# analog_frontend.net
KiCad netlist of a schematic drawn in EAGLE
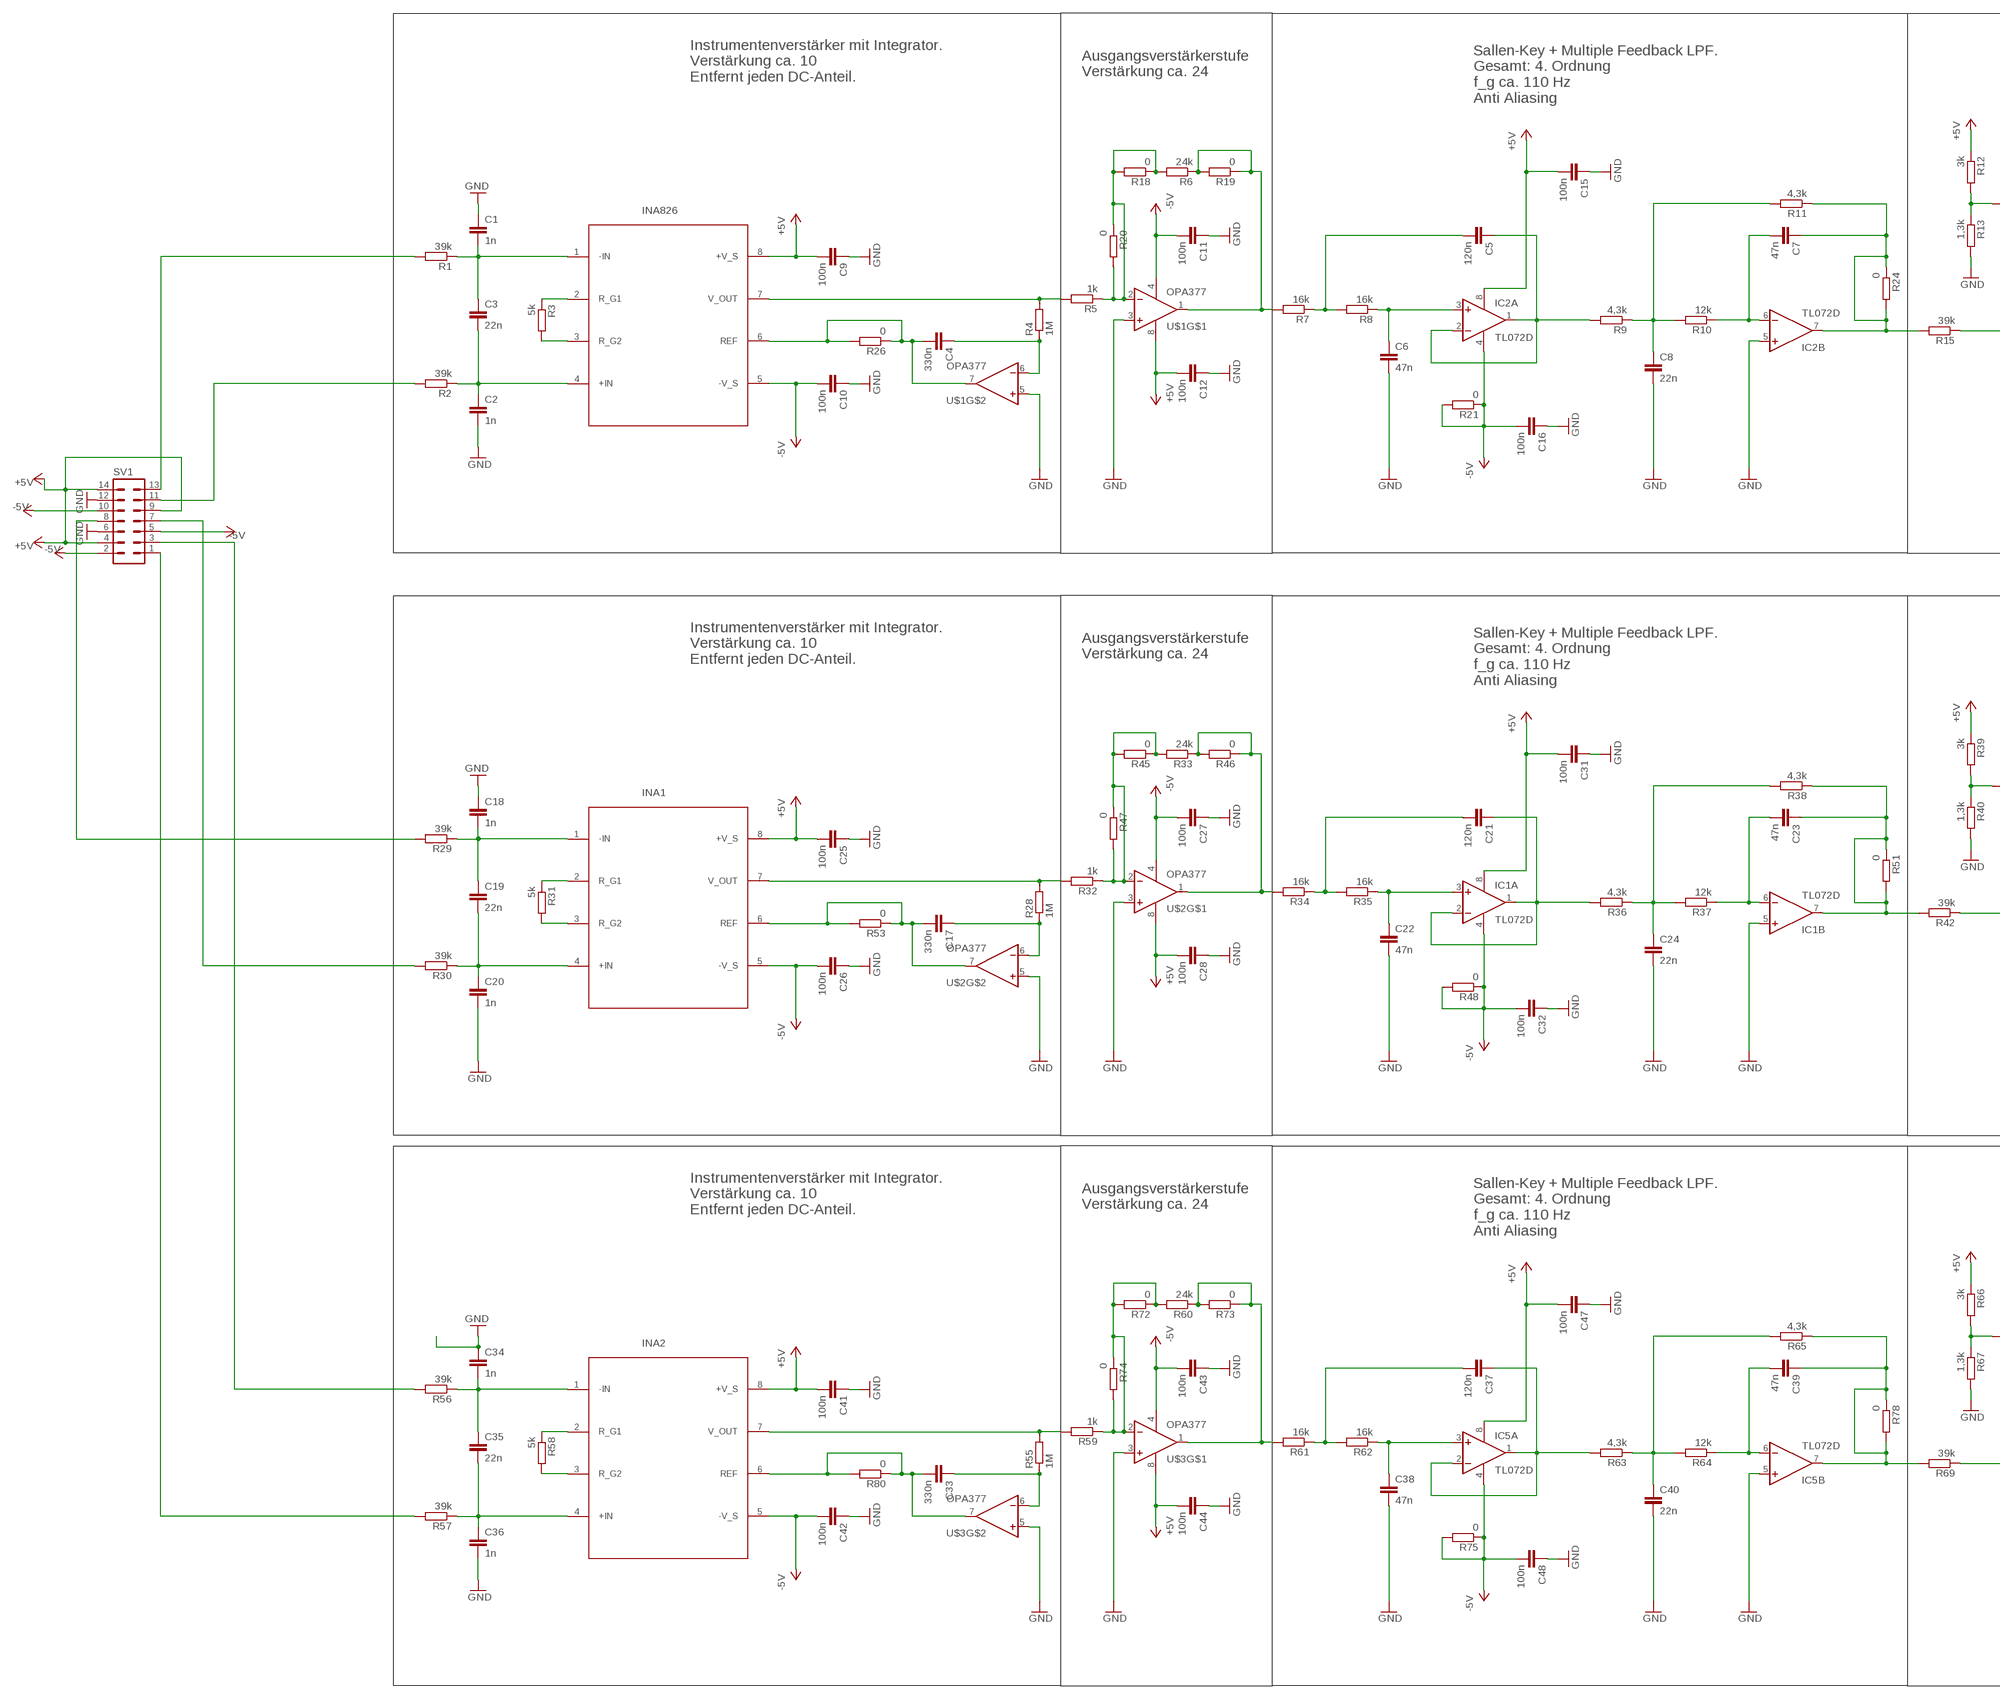
[diagram p0: schematic, sheet 1, part 1 of 2]
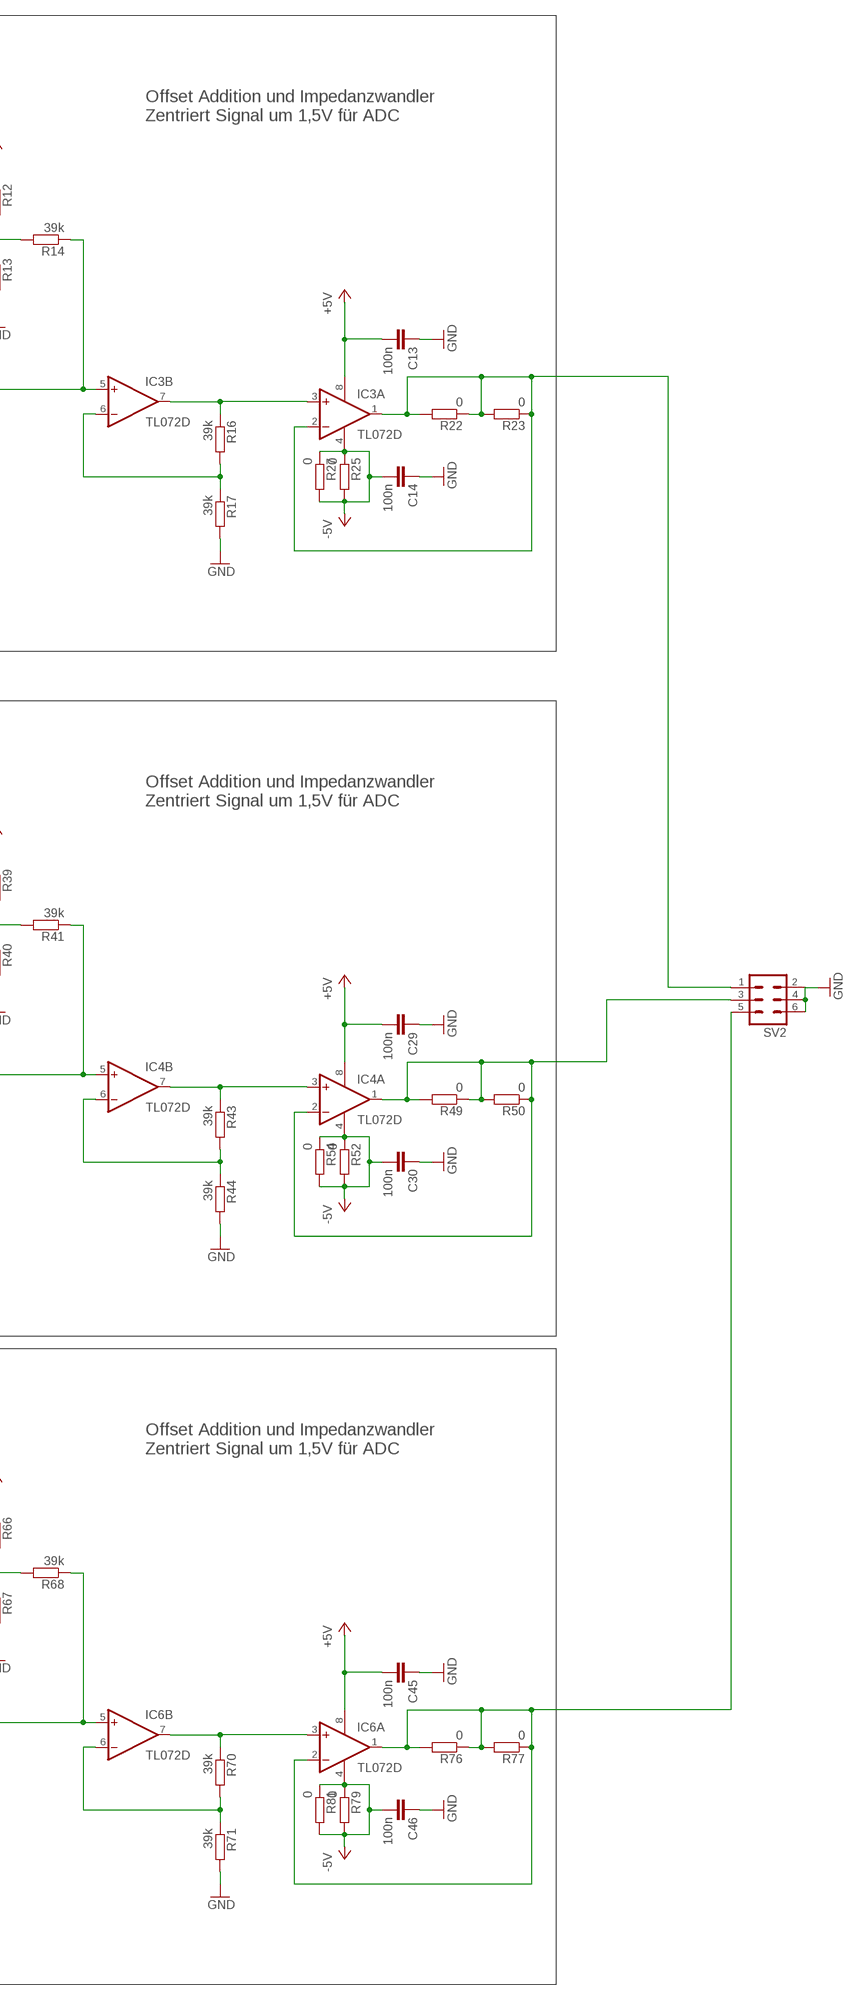
[diagram p1: schematic, sheet 1, part 2 of 2]

(export (version "E")
  (design (tool "Eeschema 10.0.6"))
  (components
    (comp (ref "C1")
      (value "1n")
      (footprint "eagle-import:C0805")
      (libsource (lib "eagle-import") (part "C-EUC0805"))
    )
    (comp (ref "C2")
      (value "1n")
      (footprint "eagle-import:C0805")
      (libsource (lib "eagle-import") (part "C-EUC0805"))
    )
    (comp (ref "C3")
      (value "22n")
      (footprint "eagle-import:C0805")
      (libsource (lib "eagle-import") (part "C-EUC0805"))
    )
    (comp (ref "C4")
      (value "330n")
      (footprint "eagle-import:C1206")
      (libsource (lib "eagle-import") (part "C-EUC1206"))
    )
    (comp (ref "C5")
      (value "120n")
      (footprint "eagle-import:C0805")
      (libsource (lib "eagle-import") (part "C-EUC0805"))
    )
    (comp (ref "C6")
      (value "47n")
      (footprint "eagle-import:C0805")
      (libsource (lib "eagle-import") (part "C-EUC0805"))
    )
    (comp (ref "C7")
      (value "47n")
      (footprint "eagle-import:C0805")
      (libsource (lib "eagle-import") (part "C-EUC0805"))
    )
    (comp (ref "C8")
      (value "22n")
      (footprint "eagle-import:C0805")
      (libsource (lib "eagle-import") (part "C-EUC0805"))
    )
    (comp (ref "C9")
      (value "100n")
      (footprint "eagle-import:C0805")
      (libsource (lib "eagle-import") (part "C-EUC0805"))
    )
    (comp (ref "C10")
      (value "100n")
      (footprint "eagle-import:C0805")
      (libsource (lib "eagle-import") (part "C-EUC0805"))
    )
    (comp (ref "C11")
      (value "100n")
      (footprint "eagle-import:C0805")
      (libsource (lib "eagle-import") (part "C-EUC0805"))
    )
    (comp (ref "C12")
      (value "100n")
      (footprint "eagle-import:C0805")
      (libsource (lib "eagle-import") (part "C-EUC0805"))
    )
    (comp (ref "C13")
      (value "100n")
      (footprint "eagle-import:C0805")
      (libsource (lib "eagle-import") (part "C-EUC0805"))
    )
    (comp (ref "C14")
      (value "100n")
      (footprint "eagle-import:C0805")
      (libsource (lib "eagle-import") (part "C-EUC0805"))
    )
    (comp (ref "C15")
      (value "100n")
      (footprint "eagle-import:C1206")
      (libsource (lib "eagle-import") (part "C-EUC1206"))
    )
    (comp (ref "C16")
      (value "100n")
      (footprint "eagle-import:C0805")
      (libsource (lib "eagle-import") (part "C-EUC0805"))
    )
    (comp (ref "C17")
      (value "330n")
      (footprint "eagle-import:C1206")
      (libsource (lib "eagle-import") (part "C-EUC1206"))
    )
    (comp (ref "C18")
      (value "1n")
      (footprint "eagle-import:C0805")
      (libsource (lib "eagle-import") (part "C-EUC0805"))
    )
    (comp (ref "C19")
      (value "22n")
      (footprint "eagle-import:C0805")
      (libsource (lib "eagle-import") (part "C-EUC0805"))
    )
    (comp (ref "C20")
      (value "1n")
      (footprint "eagle-import:C0805")
      (libsource (lib "eagle-import") (part "C-EUC0805"))
    )
    (comp (ref "C21")
      (value "120n")
      (footprint "eagle-import:C0805")
      (libsource (lib "eagle-import") (part "C-EUC0805"))
    )
    (comp (ref "C22")
      (value "47n")
      (footprint "eagle-import:C0805")
      (libsource (lib "eagle-import") (part "C-EUC0805"))
    )
    (comp (ref "C23")
      (value "47n")
      (footprint "eagle-import:C0805")
      (libsource (lib "eagle-import") (part "C-EUC0805"))
    )
    (comp (ref "C24")
      (value "22n")
      (footprint "eagle-import:C0805")
      (libsource (lib "eagle-import") (part "C-EUC0805"))
    )
    (comp (ref "C25")
      (value "100n")
      (footprint "eagle-import:C0805")
      (libsource (lib "eagle-import") (part "C-EUC0805"))
    )
    (comp (ref "C26")
      (value "100n")
      (footprint "eagle-import:C0805")
      (libsource (lib "eagle-import") (part "C-EUC0805"))
    )
    (comp (ref "C27")
      (value "100n")
      (footprint "eagle-import:C0805")
      (libsource (lib "eagle-import") (part "C-EUC0805"))
    )
    (comp (ref "C28")
      (value "100n")
      (footprint "eagle-import:C0805")
      (libsource (lib "eagle-import") (part "C-EUC0805"))
    )
    (comp (ref "C29")
      (value "100n")
      (footprint "eagle-import:C0805")
      (libsource (lib "eagle-import") (part "C-EUC0805"))
    )
    (comp (ref "C30")
      (value "100n")
      (footprint "eagle-import:C0805")
      (libsource (lib "eagle-import") (part "C-EUC0805"))
    )
    (comp (ref "C31")
      (value "100n")
      (footprint "eagle-import:C1206")
      (libsource (lib "eagle-import") (part "C-EUC1206"))
    )
    (comp (ref "C32")
      (value "100n")
      (footprint "eagle-import:C0805")
      (libsource (lib "eagle-import") (part "C-EUC0805"))
    )
    (comp (ref "C33")
      (value "330n")
      (footprint "eagle-import:C1206")
      (libsource (lib "eagle-import") (part "C-EUC1206"))
    )
    (comp (ref "C34")
      (value "1n")
      (footprint "eagle-import:C0805")
      (libsource (lib "eagle-import") (part "C-EUC0805"))
    )
    (comp (ref "C35")
      (value "22n")
      (footprint "eagle-import:C0805")
      (libsource (lib "eagle-import") (part "C-EUC0805"))
    )
    (comp (ref "C36")
      (value "1n")
      (footprint "eagle-import:C0805")
      (libsource (lib "eagle-import") (part "C-EUC0805"))
    )
    (comp (ref "C37")
      (value "120n")
      (footprint "eagle-import:C0805")
      (libsource (lib "eagle-import") (part "C-EUC0805"))
    )
    (comp (ref "C38")
      (value "47n")
      (footprint "eagle-import:C0805")
      (libsource (lib "eagle-import") (part "C-EUC0805"))
    )
    (comp (ref "C39")
      (value "47n")
      (footprint "eagle-import:C0805")
      (libsource (lib "eagle-import") (part "C-EUC0805"))
    )
    (comp (ref "C40")
      (value "22n")
      (footprint "eagle-import:C0805")
      (libsource (lib "eagle-import") (part "C-EUC0805"))
    )
    (comp (ref "C41")
      (value "100n")
      (footprint "eagle-import:C0805")
      (libsource (lib "eagle-import") (part "C-EUC0805"))
    )
    (comp (ref "C42")
      (value "100n")
      (footprint "eagle-import:C0805")
      (libsource (lib "eagle-import") (part "C-EUC0805"))
    )
    (comp (ref "C43")
      (value "100n")
      (footprint "eagle-import:C0805")
      (libsource (lib "eagle-import") (part "C-EUC0805"))
    )
    (comp (ref "C44")
      (value "100n")
      (footprint "eagle-import:C0805")
      (libsource (lib "eagle-import") (part "C-EUC0805"))
    )
    (comp (ref "C45")
      (value "100n")
      (footprint "eagle-import:C0805")
      (libsource (lib "eagle-import") (part "C-EUC0805"))
    )
    (comp (ref "C46")
      (value "100n")
      (footprint "eagle-import:C0805")
      (libsource (lib "eagle-import") (part "C-EUC0805"))
    )
    (comp (ref "C47")
      (value "100n")
      (footprint "eagle-import:C1206")
      (libsource (lib "eagle-import") (part "C-EUC1206"))
    )
    (comp (ref "C48")
      (value "100n")
      (footprint "eagle-import:C0805")
      (libsource (lib "eagle-import") (part "C-EUC0805"))
    )
    (comp (ref "IC1")
      (value "TL072D")
      (footprint "eagle-import:SO08")
      (libsource (lib "eagle-import") (part "TL072D"))
    )
    (comp (ref "IC2")
      (value "TL072D")
      (footprint "eagle-import:SO08")
      (libsource (lib "eagle-import") (part "TL072D"))
    )
    (comp (ref "IC3")
      (value "TL072D")
      (footprint "eagle-import:SO08")
      (libsource (lib "eagle-import") (part "TL072D"))
    )
    (comp (ref "IC4")
      (value "TL072D")
      (footprint "eagle-import:SO08")
      (libsource (lib "eagle-import") (part "TL072D"))
    )
    (comp (ref "IC5")
      (value "TL072D")
      (footprint "eagle-import:SO08")
      (libsource (lib "eagle-import") (part "TL072D"))
    )
    (comp (ref "IC6")
      (value "TL072D")
      (footprint "eagle-import:SO08")
      (libsource (lib "eagle-import") (part "TL072D"))
    )
    (comp (ref "INA1")
      (value "INA826")
      (footprint "eagle-import:SOIC8")
      (libsource (lib "eagle-import") (part "INA826"))
    )
    (comp (ref "INA2")
      (value "INA826")
      (footprint "eagle-import:SOIC8")
      (libsource (lib "eagle-import") (part "INA826"))
    )
    (comp (ref "INA826")
      (value "INA826")
      (footprint "eagle-import:SOIC8")
      (libsource (lib "eagle-import") (part "INA826"))
    )
    (comp (ref "R1")
      (value "39k")
      (footprint "eagle-import:R0805")
      (libsource (lib "eagle-import") (part "R-EU_R0805"))
    )
    (comp (ref "R2")
      (value "39k")
      (footprint "eagle-import:R0805")
      (libsource (lib "eagle-import") (part "R-EU_R0805"))
    )
    (comp (ref "R3")
      (value "5k")
      (footprint "eagle-import:R0805")
      (libsource (lib "eagle-import") (part "R-EU_R0805"))
    )
    (comp (ref "R4")
      (value "1M")
      (footprint "eagle-import:R1206")
      (libsource (lib "eagle-import") (part "R-EU_R1206"))
    )
    (comp (ref "R5")
      (value "1k")
      (footprint "eagle-import:R1206")
      (libsource (lib "eagle-import") (part "R-EU_R1206"))
    )
    (comp (ref "R6")
      (value "24k")
      (footprint "eagle-import:R0805")
      (libsource (lib "eagle-import") (part "R-EU_R0805"))
    )
    (comp (ref "R7")
      (value "16k")
      (footprint "eagle-import:R1206")
      (libsource (lib "eagle-import") (part "R-EU_R1206"))
    )
    (comp (ref "R8")
      (value "16k")
      (footprint "eagle-import:R0805")
      (libsource (lib "eagle-import") (part "R-EU_R0805"))
    )
    (comp (ref "R9")
      (value "4,3k")
      (footprint "eagle-import:R0805")
      (libsource (lib "eagle-import") (part "R-EU_R0805"))
    )
    (comp (ref "R10")
      (value "12k")
      (footprint "eagle-import:R0805")
      (libsource (lib "eagle-import") (part "R-EU_R0805"))
    )
    (comp (ref "R11")
      (value "4,3k")
      (footprint "eagle-import:R0805")
      (libsource (lib "eagle-import") (part "R-EU_R0805"))
    )
    (comp (ref "R12")
      (value "3k")
      (footprint "eagle-import:R0805")
      (libsource (lib "eagle-import") (part "R-EU_R0805"))
    )
    (comp (ref "R13")
      (value "1,3k")
      (footprint "eagle-import:R1206")
      (libsource (lib "eagle-import") (part "R-EU_R1206"))
    )
    (comp (ref "R14")
      (value "39k")
      (footprint "eagle-import:R0805")
      (libsource (lib "eagle-import") (part "R-EU_R0805"))
    )
    (comp (ref "R15")
      (value "39k")
      (footprint "eagle-import:R0805")
      (libsource (lib "eagle-import") (part "R-EU_R0805"))
    )
    (comp (ref "R16")
      (value "39k")
      (footprint "eagle-import:R0805")
      (libsource (lib "eagle-import") (part "R-EU_R0805"))
    )
    (comp (ref "R17")
      (value "39k")
      (footprint "eagle-import:R1206")
      (libsource (lib "eagle-import") (part "R-EU_R1206"))
    )
    (comp (ref "R18")
      (value "0")
      (footprint "eagle-import:R1206")
      (libsource (lib "eagle-import") (part "R-EU_R1206"))
    )
    (comp (ref "R19")
      (value "0")
      (footprint "eagle-import:R1206")
      (libsource (lib "eagle-import") (part "R-EU_R1206"))
    )
    (comp (ref "R20")
      (value "0")
      (footprint "eagle-import:R1206")
      (libsource (lib "eagle-import") (part "R-EU_R1206"))
    )
    (comp (ref "R21")
      (value "0")
      (footprint "eagle-import:R1206")
      (libsource (lib "eagle-import") (part "R-EU_R1206"))
    )
    (comp (ref "R22")
      (value "0")
      (footprint "eagle-import:R1206")
      (libsource (lib "eagle-import") (part "R-EU_R1206"))
    )
    (comp (ref "R23")
      (value "0")
      (footprint "eagle-import:R1206")
      (libsource (lib "eagle-import") (part "R-EU_R1206"))
    )
    (comp (ref "R24")
      (value "0")
      (footprint "eagle-import:R1206")
      (libsource (lib "eagle-import") (part "R-EU_R1206"))
    )
    (comp (ref "R25")
      (value "0")
      (footprint "eagle-import:R1206")
      (libsource (lib "eagle-import") (part "R-EU_R1206"))
    )
    (comp (ref "R26")
      (value "0")
      (footprint "eagle-import:R1206")
      (libsource (lib "eagle-import") (part "R-EU_R1206"))
    )
    (comp (ref "R27")
      (value "0")
      (footprint "eagle-import:R1206")
      (libsource (lib "eagle-import") (part "R-EU_R1206"))
    )
    (comp (ref "R28")
      (value "1M")
      (footprint "eagle-import:R1206")
      (libsource (lib "eagle-import") (part "R-EU_R1206"))
    )
    (comp (ref "R29")
      (value "39k")
      (footprint "eagle-import:R0805")
      (libsource (lib "eagle-import") (part "R-EU_R0805"))
    )
    (comp (ref "R30")
      (value "39k")
      (footprint "eagle-import:R0805")
      (libsource (lib "eagle-import") (part "R-EU_R0805"))
    )
    (comp (ref "R31")
      (value "5k")
      (footprint "eagle-import:R0805")
      (libsource (lib "eagle-import") (part "R-EU_R0805"))
    )
    (comp (ref "R32")
      (value "1k")
      (footprint "eagle-import:R1206")
      (libsource (lib "eagle-import") (part "R-EU_R1206"))
    )
    (comp (ref "R33")
      (value "24k")
      (footprint "eagle-import:R0805")
      (libsource (lib "eagle-import") (part "R-EU_R0805"))
    )
    (comp (ref "R34")
      (value "16k")
      (footprint "eagle-import:R1206")
      (libsource (lib "eagle-import") (part "R-EU_R1206"))
    )
    (comp (ref "R35")
      (value "16k")
      (footprint "eagle-import:R0805")
      (libsource (lib "eagle-import") (part "R-EU_R0805"))
    )
    (comp (ref "R36")
      (value "4,3k")
      (footprint "eagle-import:R0805")
      (libsource (lib "eagle-import") (part "R-EU_R0805"))
    )
    (comp (ref "R37")
      (value "12k")
      (footprint "eagle-import:R0805")
      (libsource (lib "eagle-import") (part "R-EU_R0805"))
    )
    (comp (ref "R38")
      (value "4,3k")
      (footprint "eagle-import:R0805")
      (libsource (lib "eagle-import") (part "R-EU_R0805"))
    )
    (comp (ref "R39")
      (value "3k")
      (footprint "eagle-import:R0805")
      (libsource (lib "eagle-import") (part "R-EU_R0805"))
    )
    (comp (ref "R40")
      (value "1,3k")
      (footprint "eagle-import:R1206")
      (libsource (lib "eagle-import") (part "R-EU_R1206"))
    )
    (comp (ref "R41")
      (value "39k")
      (footprint "eagle-import:R0805")
      (libsource (lib "eagle-import") (part "R-EU_R0805"))
    )
    (comp (ref "R42")
      (value "39k")
      (footprint "eagle-import:R0805")
      (libsource (lib "eagle-import") (part "R-EU_R0805"))
    )
    (comp (ref "R43")
      (value "39k")
      (footprint "eagle-import:R0805")
      (libsource (lib "eagle-import") (part "R-EU_R0805"))
    )
    (comp (ref "R44")
      (value "39k")
      (footprint "eagle-import:R1206")
      (libsource (lib "eagle-import") (part "R-EU_R1206"))
    )
    (comp (ref "R45")
      (value "0")
      (footprint "eagle-import:R1206")
      (libsource (lib "eagle-import") (part "R-EU_R1206"))
    )
    (comp (ref "R46")
      (value "0")
      (footprint "eagle-import:R1206")
      (libsource (lib "eagle-import") (part "R-EU_R1206"))
    )
    (comp (ref "R47")
      (value "0")
      (footprint "eagle-import:R1206")
      (libsource (lib "eagle-import") (part "R-EU_R1206"))
    )
    (comp (ref "R48")
      (value "0")
      (footprint "eagle-import:R1206")
      (libsource (lib "eagle-import") (part "R-EU_R1206"))
    )
    (comp (ref "R49")
      (value "0")
      (footprint "eagle-import:R1206")
      (libsource (lib "eagle-import") (part "R-EU_R1206"))
    )
    (comp (ref "R50")
      (value "0")
      (footprint "eagle-import:R1206")
      (libsource (lib "eagle-import") (part "R-EU_R1206"))
    )
    (comp (ref "R51")
      (value "0")
      (footprint "eagle-import:R1206")
      (libsource (lib "eagle-import") (part "R-EU_R1206"))
    )
    (comp (ref "R52")
      (value "0")
      (footprint "eagle-import:R1206")
      (libsource (lib "eagle-import") (part "R-EU_R1206"))
    )
    (comp (ref "R53")
      (value "0")
      (footprint "eagle-import:R1206")
      (libsource (lib "eagle-import") (part "R-EU_R1206"))
    )
    (comp (ref "R54")
      (value "0")
      (footprint "eagle-import:R1206")
      (libsource (lib "eagle-import") (part "R-EU_R1206"))
    )
    (comp (ref "R55")
      (value "1M")
      (footprint "eagle-import:R1206")
      (libsource (lib "eagle-import") (part "R-EU_R1206"))
    )
    (comp (ref "R56")
      (value "39k")
      (footprint "eagle-import:R0805")
      (libsource (lib "eagle-import") (part "R-EU_R0805"))
    )
    (comp (ref "R57")
      (value "39k")
      (footprint "eagle-import:R0805")
      (libsource (lib "eagle-import") (part "R-EU_R0805"))
    )
    (comp (ref "R58")
      (value "5k")
      (footprint "eagle-import:R0805")
      (libsource (lib "eagle-import") (part "R-EU_R0805"))
    )
    (comp (ref "R59")
      (value "1k")
      (footprint "eagle-import:R1206")
      (libsource (lib "eagle-import") (part "R-EU_R1206"))
    )
    (comp (ref "R60")
      (value "24k")
      (footprint "eagle-import:R0805")
      (libsource (lib "eagle-import") (part "R-EU_R0805"))
    )
    (comp (ref "R61")
      (value "16k")
      (footprint "eagle-import:R1206")
      (libsource (lib "eagle-import") (part "R-EU_R1206"))
    )
    (comp (ref "R62")
      (value "16k")
      (footprint "eagle-import:R0805")
      (libsource (lib "eagle-import") (part "R-EU_R0805"))
    )
    (comp (ref "R63")
      (value "4,3k")
      (footprint "eagle-import:R0805")
      (libsource (lib "eagle-import") (part "R-EU_R0805"))
    )
    (comp (ref "R64")
      (value "12k")
      (footprint "eagle-import:R0805")
      (libsource (lib "eagle-import") (part "R-EU_R0805"))
    )
    (comp (ref "R65")
      (value "4,3k")
      (footprint "eagle-import:R0805")
      (libsource (lib "eagle-import") (part "R-EU_R0805"))
    )
    (comp (ref "R66")
      (value "3k")
      (footprint "eagle-import:R0805")
      (libsource (lib "eagle-import") (part "R-EU_R0805"))
    )
    (comp (ref "R67")
      (value "1,3k")
      (footprint "eagle-import:R1206")
      (libsource (lib "eagle-import") (part "R-EU_R1206"))
    )
    (comp (ref "R68")
      (value "39k")
      (footprint "eagle-import:R0805")
      (libsource (lib "eagle-import") (part "R-EU_R0805"))
    )
    (comp (ref "R69")
      (value "39k")
      (footprint "eagle-import:R0805")
      (libsource (lib "eagle-import") (part "R-EU_R0805"))
    )
    (comp (ref "R70")
      (value "39k")
      (footprint "eagle-import:R0805")
      (libsource (lib "eagle-import") (part "R-EU_R0805"))
    )
    (comp (ref "R71")
      (value "39k")
      (footprint "eagle-import:R1206")
      (libsource (lib "eagle-import") (part "R-EU_R1206"))
    )
    (comp (ref "R72")
      (value "0")
      (footprint "eagle-import:R1206")
      (libsource (lib "eagle-import") (part "R-EU_R1206"))
    )
    (comp (ref "R73")
      (value "0")
      (footprint "eagle-import:R1206")
      (libsource (lib "eagle-import") (part "R-EU_R1206"))
    )
    (comp (ref "R74")
      (value "0")
      (footprint "eagle-import:R1206")
      (libsource (lib "eagle-import") (part "R-EU_R1206"))
    )
    (comp (ref "R75")
      (value "0")
      (footprint "eagle-import:R1206")
      (libsource (lib "eagle-import") (part "R-EU_R1206"))
    )
    (comp (ref "R76")
      (value "0")
      (footprint "eagle-import:R1206")
      (libsource (lib "eagle-import") (part "R-EU_R1206"))
    )
    (comp (ref "R77")
      (value "0")
      (footprint "eagle-import:R1206")
      (libsource (lib "eagle-import") (part "R-EU_R1206"))
    )
    (comp (ref "R78")
      (value "0")
      (footprint "eagle-import:R1206")
      (libsource (lib "eagle-import") (part "R-EU_R1206"))
    )
    (comp (ref "R79")
      (value "0")
      (footprint "eagle-import:R1206")
      (libsource (lib "eagle-import") (part "R-EU_R1206"))
    )
    (comp (ref "R80")
      (value "0")
      (footprint "eagle-import:R1206")
      (libsource (lib "eagle-import") (part "R-EU_R1206"))
    )
    (comp (ref "R81")
      (value "0")
      (footprint "eagle-import:R1206")
      (libsource (lib "eagle-import") (part "R-EU_R1206"))
    )
    (comp (ref "SV1")
      (value "ML14L")
      (footprint "eagle-import:ML14L")
      (libsource (lib "eagle-import") (part "ML14L"))
    )
    (comp (ref "SV2")
      (value "ML6L")
      (footprint "eagle-import:ML6L")
      (libsource (lib "eagle-import") (part "ML6L"))
    )
    (comp (ref "U$1")
      (value "OPA377")
      (footprint "eagle-import:SOIC8")
      (libsource (lib "eagle-import") (part "OPA377"))
    )
    (comp (ref "U$2")
      (value "OPA377")
      (footprint "eagle-import:SOIC8")
      (libsource (lib "eagle-import") (part "OPA377"))
    )
    (comp (ref "U$3")
      (value "OPA377")
      (footprint "eagle-import:SOIC8")
      (libsource (lib "eagle-import") (part "OPA377"))
    )
  )
  (nets
    (net (code "1") (name "+5V") (class "Default")
      (node (ref "C12") (pin "2") (pinfunction "2_2") (pintype "passive"))
      (node (ref "C13") (pin "2") (pinfunction "2_2") (pintype "passive"))
      (node (ref "C15") (pin "2") (pinfunction "2_2") (pintype "passive"))
      (node (ref "C25") (pin "2") (pinfunction "2_2") (pintype "passive"))
      (node (ref "C28") (pin "2") (pinfunction "2_2") (pintype "passive"))
      (node (ref "C29") (pin "2") (pinfunction "2_2") (pintype "passive"))
      (node (ref "C31") (pin "2") (pinfunction "2_2") (pintype "passive"))
      (node (ref "C41") (pin "2") (pinfunction "2_2") (pintype "passive"))
      (node (ref "C44") (pin "2") (pinfunction "2_2") (pintype "passive"))
      (node (ref "C45") (pin "2") (pinfunction "2_2") (pintype "passive"))
      (node (ref "C47") (pin "2") (pinfunction "2_2") (pintype "passive"))
      (node (ref "C9") (pin "2") (pinfunction "2_2") (pintype "passive"))
      (node (ref "IC1") (pin "8") (pinfunction "V+_8") (pintype "power_in"))
      (node (ref "IC2") (pin "8") (pinfunction "V+_8") (pintype "power_in"))
      (node (ref "IC3") (pin "8") (pinfunction "V+_8") (pintype "power_in"))
      (node (ref "IC4") (pin "8") (pinfunction "V+_8") (pintype "power_in"))
      (node (ref "IC5") (pin "8") (pinfunction "V+_8") (pintype "power_in"))
      (node (ref "IC6") (pin "8") (pinfunction "V+_8") (pintype "power_in"))
      (node (ref "INA1") (pin "8") (pinfunction "+V_S_8") (pintype "power_in"))
      (node (ref "INA2") (pin "8") (pinfunction "+V_S_8") (pintype "power_in"))
      (node (ref "INA826") (pin "8") (pinfunction "+V_S_8") (pintype "power_in"))
      (node (ref "R12") (pin "1") (pinfunction "1_1") (pintype "passive"))
      (node (ref "R39") (pin "1") (pinfunction "1_1") (pintype "passive"))
      (node (ref "R66") (pin "1") (pinfunction "1_1") (pintype "passive"))
      (node (ref "SV1") (pin "14") (pinfunction "14_14") (pintype "passive"))
      (node (ref "SV1") (pin "4") (pinfunction "4_4") (pintype "passive"))
      (node (ref "SV1") (pin "9") (pinfunction "9_9") (pintype "passive"))
      (node (ref "U$1") (pin "8") (pinfunction "V+_8") (pintype "power_in"))
      (node (ref "U$2") (pin "8") (pinfunction "V+_8") (pintype "power_in"))
      (node (ref "U$3") (pin "8") (pinfunction "V+_8") (pintype "power_in"))
    )
    (net (code "2") (name "-5V") (class "Default")
      (node (ref "C10") (pin "2") (pinfunction "2_2") (pintype "passive"))
      (node (ref "C11") (pin "2") (pinfunction "2_2") (pintype "passive"))
      (node (ref "C14") (pin "2") (pinfunction "2_2") (pintype "passive"))
      (node (ref "C16") (pin "2") (pinfunction "2_2") (pintype "passive"))
      (node (ref "C26") (pin "2") (pinfunction "2_2") (pintype "passive"))
      (node (ref "C27") (pin "2") (pinfunction "2_2") (pintype "passive"))
      (node (ref "C30") (pin "2") (pinfunction "2_2") (pintype "passive"))
      (node (ref "C32") (pin "2") (pinfunction "2_2") (pintype "passive"))
      (node (ref "C42") (pin "2") (pinfunction "2_2") (pintype "passive"))
      (node (ref "C43") (pin "2") (pinfunction "2_2") (pintype "passive"))
      (node (ref "C46") (pin "2") (pinfunction "2_2") (pintype "passive"))
      (node (ref "C48") (pin "2") (pinfunction "2_2") (pintype "passive"))
      (node (ref "IC1") (pin "4") (pinfunction "V-_4") (pintype "power_in"))
      (node (ref "IC2") (pin "4") (pinfunction "V-_4") (pintype "power_in"))
      (node (ref "IC3") (pin "4") (pinfunction "V-_4") (pintype "power_in"))
      (node (ref "IC4") (pin "4") (pinfunction "V-_4") (pintype "power_in"))
      (node (ref "IC5") (pin "4") (pinfunction "V-_4") (pintype "power_in"))
      (node (ref "IC6") (pin "4") (pinfunction "V-_4") (pintype "power_in"))
      (node (ref "INA1") (pin "5") (pinfunction "-V_S_5") (pintype "power_in"))
      (node (ref "INA2") (pin "5") (pinfunction "-V_S_5") (pintype "power_in"))
      (node (ref "INA826") (pin "5") (pinfunction "-V_S_5") (pintype "power_in"))
      (node (ref "R21") (pin "1") (pinfunction "1_1") (pintype "passive"))
      (node (ref "R21") (pin "2") (pinfunction "2_2") (pintype "passive"))
      (node (ref "R25") (pin "1") (pinfunction "1_1") (pintype "passive"))
      (node (ref "R25") (pin "2") (pinfunction "2_2") (pintype "passive"))
      (node (ref "R27") (pin "1") (pinfunction "1_1") (pintype "passive"))
      (node (ref "R27") (pin "2") (pinfunction "2_2") (pintype "passive"))
      (node (ref "R48") (pin "1") (pinfunction "1_1") (pintype "passive"))
      (node (ref "R48") (pin "2") (pinfunction "2_2") (pintype "passive"))
      (node (ref "R52") (pin "1") (pinfunction "1_1") (pintype "passive"))
      (node (ref "R52") (pin "2") (pinfunction "2_2") (pintype "passive"))
      (node (ref "R54") (pin "1") (pinfunction "1_1") (pintype "passive"))
      (node (ref "R54") (pin "2") (pinfunction "2_2") (pintype "passive"))
      (node (ref "R75") (pin "1") (pinfunction "1_1") (pintype "passive"))
      (node (ref "R75") (pin "2") (pinfunction "2_2") (pintype "passive"))
      (node (ref "R79") (pin "1") (pinfunction "1_1") (pintype "passive"))
      (node (ref "R79") (pin "2") (pinfunction "2_2") (pintype "passive"))
      (node (ref "R81") (pin "1") (pinfunction "1_1") (pintype "passive"))
      (node (ref "R81") (pin "2") (pinfunction "2_2") (pintype "passive"))
      (node (ref "SV1") (pin "10") (pinfunction "10_10") (pintype "passive"))
      (node (ref "SV1") (pin "2") (pinfunction "2_2") (pintype "passive"))
      (node (ref "SV1") (pin "5") (pinfunction "5_5") (pintype "passive"))
      (node (ref "U$1") (pin "4") (pinfunction "V-_4") (pintype "power_in"))
      (node (ref "U$2") (pin "4") (pinfunction "V-_4") (pintype "power_in"))
      (node (ref "U$3") (pin "4") (pinfunction "V-_4") (pintype "power_in"))
    )
    (net (code "3") (name "GND") (class "Default")
      (node (ref "C1") (pin "1") (pinfunction "1_1") (pintype "passive"))
      (node (ref "C10") (pin "1") (pinfunction "1_1") (pintype "passive"))
      (node (ref "C11") (pin "1") (pinfunction "1_1") (pintype "passive"))
      (node (ref "C12") (pin "1") (pinfunction "1_1") (pintype "passive"))
      (node (ref "C13") (pin "1") (pinfunction "1_1") (pintype "passive"))
      (node (ref "C14") (pin "1") (pinfunction "1_1") (pintype "passive"))
      (node (ref "C15") (pin "1") (pinfunction "1_1") (pintype "passive"))
      (node (ref "C16") (pin "1") (pinfunction "1_1") (pintype "passive"))
      (node (ref "C18") (pin "1") (pinfunction "1_1") (pintype "passive"))
      (node (ref "C2") (pin "2") (pinfunction "2_2") (pintype "passive"))
      (node (ref "C20") (pin "2") (pinfunction "2_2") (pintype "passive"))
      (node (ref "C22") (pin "2") (pinfunction "2_2") (pintype "passive"))
      (node (ref "C24") (pin "2") (pinfunction "2_2") (pintype "passive"))
      (node (ref "C25") (pin "1") (pinfunction "1_1") (pintype "passive"))
      (node (ref "C26") (pin "1") (pinfunction "1_1") (pintype "passive"))
      (node (ref "C27") (pin "1") (pinfunction "1_1") (pintype "passive"))
      (node (ref "C28") (pin "1") (pinfunction "1_1") (pintype "passive"))
      (node (ref "C29") (pin "1") (pinfunction "1_1") (pintype "passive"))
      (node (ref "C30") (pin "1") (pinfunction "1_1") (pintype "passive"))
      (node (ref "C31") (pin "1") (pinfunction "1_1") (pintype "passive"))
      (node (ref "C32") (pin "1") (pinfunction "1_1") (pintype "passive"))
      (node (ref "C34") (pin "1") (pinfunction "1_1") (pintype "passive"))
      (node (ref "C36") (pin "2") (pinfunction "2_2") (pintype "passive"))
      (node (ref "C38") (pin "2") (pinfunction "2_2") (pintype "passive"))
      (node (ref "C40") (pin "2") (pinfunction "2_2") (pintype "passive"))
      (node (ref "C41") (pin "1") (pinfunction "1_1") (pintype "passive"))
      (node (ref "C42") (pin "1") (pinfunction "1_1") (pintype "passive"))
      (node (ref "C43") (pin "1") (pinfunction "1_1") (pintype "passive"))
      (node (ref "C44") (pin "1") (pinfunction "1_1") (pintype "passive"))
      (node (ref "C45") (pin "1") (pinfunction "1_1") (pintype "passive"))
      (node (ref "C46") (pin "1") (pinfunction "1_1") (pintype "passive"))
      (node (ref "C47") (pin "1") (pinfunction "1_1") (pintype "passive"))
      (node (ref "C48") (pin "1") (pinfunction "1_1") (pintype "passive"))
      (node (ref "C6") (pin "2") (pinfunction "2_2") (pintype "passive"))
      (node (ref "C8") (pin "2") (pinfunction "2_2") (pintype "passive"))
      (node (ref "C9") (pin "1") (pinfunction "1_1") (pintype "passive"))
      (node (ref "IC1") (pin "5") (pinfunction "+IN_5") (pintype "input"))
      (node (ref "IC2") (pin "5") (pinfunction "+IN_5") (pintype "input"))
      (node (ref "IC5") (pin "5") (pinfunction "+IN_5") (pintype "input"))
      (node (ref "R13") (pin "2") (pinfunction "2_2") (pintype "passive"))
      (node (ref "R17") (pin "2") (pinfunction "2_2") (pintype "passive"))
      (node (ref "R40") (pin "2") (pinfunction "2_2") (pintype "passive"))
      (node (ref "R44") (pin "2") (pinfunction "2_2") (pintype "passive"))
      (node (ref "R67") (pin "2") (pinfunction "2_2") (pintype "passive"))
      (node (ref "R71") (pin "2") (pinfunction "2_2") (pintype "passive"))
      (node (ref "SV1") (pin "12") (pinfunction "12_12") (pintype "passive"))
      (node (ref "SV1") (pin "6") (pinfunction "6_6") (pintype "passive"))
      (node (ref "SV2") (pin "2") (pinfunction "2_2") (pintype "passive"))
      (node (ref "SV2") (pin "4") (pinfunction "4_4") (pintype "passive"))
      (node (ref "SV2") (pin "6") (pinfunction "6_6") (pintype "passive"))
      (node (ref "U$1") (pin "3") (pinfunction "+IN_3") (pintype "input"))
      (node (ref "U$1") (pin "5") (pinfunction "+IN_5") (pintype "input"))
      (node (ref "U$2") (pin "3") (pinfunction "+IN_3") (pintype "input"))
      (node (ref "U$2") (pin "5") (pinfunction "+IN_5") (pintype "input"))
      (node (ref "U$3") (pin "3") (pinfunction "+IN_3") (pintype "input"))
      (node (ref "U$3") (pin "5") (pinfunction "+IN_5") (pintype "input"))
    )
    (net (code "4") (name "Net-(C5-Pad2)") (class "Default")
      (node (ref "C5") (pin "2") (pinfunction "2_2") (pintype "passive"))
      (node (ref "R7") (pin "1") (pinfunction "1_1") (pintype "passive"))
      (node (ref "R8") (pin "2") (pinfunction "2_2") (pintype "passive"))
    )
    (net (code "5") (name "Net-(C8-Pad1)") (class "Default")
      (node (ref "C8") (pin "1") (pinfunction "1_1") (pintype "passive"))
      (node (ref "R10") (pin "2") (pinfunction "2_2") (pintype "passive"))
      (node (ref "R11") (pin "2") (pinfunction "2_2") (pintype "passive"))
      (node (ref "R9") (pin "1") (pinfunction "1_1") (pintype "passive"))
    )
    (net (code "6") (name "Net-(C21-Pad2)") (class "Default")
      (node (ref "C21") (pin "2") (pinfunction "2_2") (pintype "passive"))
      (node (ref "R34") (pin "1") (pinfunction "1_1") (pintype "passive"))
      (node (ref "R35") (pin "2") (pinfunction "2_2") (pintype "passive"))
    )
    (net (code "7") (name "Net-(C24-Pad1)") (class "Default")
      (node (ref "C24") (pin "1") (pinfunction "1_1") (pintype "passive"))
      (node (ref "R36") (pin "1") (pinfunction "1_1") (pintype "passive"))
      (node (ref "R37") (pin "2") (pinfunction "2_2") (pintype "passive"))
      (node (ref "R38") (pin "2") (pinfunction "2_2") (pintype "passive"))
    )
    (net (code "8") (name "Net-(C37-Pad2)") (class "Default")
      (node (ref "C37") (pin "2") (pinfunction "2_2") (pintype "passive"))
      (node (ref "R61") (pin "1") (pinfunction "1_1") (pintype "passive"))
      (node (ref "R62") (pin "2") (pinfunction "2_2") (pintype "passive"))
    )
    (net (code "9") (name "Net-(C40-Pad1)") (class "Default")
      (node (ref "C40") (pin "1") (pinfunction "1_1") (pintype "passive"))
      (node (ref "R63") (pin "1") (pinfunction "1_1") (pintype "passive"))
      (node (ref "R64") (pin "2") (pinfunction "2_2") (pintype "passive"))
      (node (ref "R65") (pin "2") (pinfunction "2_2") (pintype "passive"))
    )
    (net (code "10") (name "Net-(IC1A-+IN)") (class "Default")
      (node (ref "C22") (pin "1") (pinfunction "1_1") (pintype "passive"))
      (node (ref "IC1") (pin "3") (pinfunction "+IN_3") (pintype "input"))
      (node (ref "R35") (pin "1") (pinfunction "1_1") (pintype "passive"))
    )
    (net (code "11") (name "Net-(IC1A--IN)") (class "Default")
      (node (ref "C21") (pin "1") (pinfunction "1_1") (pintype "passive"))
      (node (ref "IC1") (pin "1") (pinfunction "OUT_1") (pintype "output"))
      (node (ref "IC1") (pin "2") (pinfunction "-IN_2") (pintype "input"))
      (node (ref "R36") (pin "2") (pinfunction "2_2") (pintype "passive"))
    )
    (net (code "12") (name "Net-(IC1B--IN)") (class "Default")
      (node (ref "C23") (pin "2") (pinfunction "2_2") (pintype "passive"))
      (node (ref "IC1") (pin "6") (pinfunction "-IN_6") (pintype "input"))
      (node (ref "R37") (pin "1") (pinfunction "1_1") (pintype "passive"))
    )
    (net (code "13") (name "Net-(IC1B-OUT)") (class "Default")
      (node (ref "C23") (pin "1") (pinfunction "1_1") (pintype "passive"))
      (node (ref "IC1") (pin "7") (pinfunction "OUT_7") (pintype "output"))
      (node (ref "R38") (pin "1") (pinfunction "1_1") (pintype "passive"))
      (node (ref "R42") (pin "2") (pinfunction "2_2") (pintype "passive"))
      (node (ref "R51") (pin "1") (pinfunction "1_1") (pintype "passive"))
      (node (ref "R51") (pin "2") (pinfunction "2_2") (pintype "passive"))
    )
    (net (code "14") (name "Net-(IC2A-+IN)") (class "Default")
      (node (ref "C6") (pin "1") (pinfunction "1_1") (pintype "passive"))
      (node (ref "IC2") (pin "3") (pinfunction "+IN_3") (pintype "input"))
      (node (ref "R8") (pin "1") (pinfunction "1_1") (pintype "passive"))
    )
    (net (code "15") (name "Net-(IC2A--IN)") (class "Default")
      (node (ref "C5") (pin "1") (pinfunction "1_1") (pintype "passive"))
      (node (ref "IC2") (pin "1") (pinfunction "OUT_1") (pintype "output"))
      (node (ref "IC2") (pin "2") (pinfunction "-IN_2") (pintype "input"))
      (node (ref "R9") (pin "2") (pinfunction "2_2") (pintype "passive"))
    )
    (net (code "16") (name "Net-(IC2B--IN)") (class "Default")
      (node (ref "C7") (pin "2") (pinfunction "2_2") (pintype "passive"))
      (node (ref "IC2") (pin "6") (pinfunction "-IN_6") (pintype "input"))
      (node (ref "R10") (pin "1") (pinfunction "1_1") (pintype "passive"))
    )
    (net (code "17") (name "Net-(IC2B-OUT)") (class "Default")
      (node (ref "C7") (pin "1") (pinfunction "1_1") (pintype "passive"))
      (node (ref "IC2") (pin "7") (pinfunction "OUT_7") (pintype "output"))
      (node (ref "R11") (pin "1") (pinfunction "1_1") (pintype "passive"))
      (node (ref "R15") (pin "2") (pinfunction "2_2") (pintype "passive"))
      (node (ref "R24") (pin "1") (pinfunction "1_1") (pintype "passive"))
      (node (ref "R24") (pin "2") (pinfunction "2_2") (pintype "passive"))
    )
    (net (code "18") (name "Net-(IC3A-+IN)") (class "Default")
      (node (ref "IC3") (pin "3") (pinfunction "+IN_3") (pintype "input"))
      (node (ref "IC3") (pin "7") (pinfunction "OUT_7") (pintype "output"))
      (node (ref "R16") (pin "1") (pinfunction "1_1") (pintype "passive"))
    )
    (net (code "19") (name "Net-(IC3A--IN)") (class "Default")
      (node (ref "IC3") (pin "1") (pinfunction "OUT_1") (pintype "output"))
      (node (ref "IC3") (pin "2") (pinfunction "-IN_2") (pintype "input"))
      (node (ref "R22") (pin "1") (pinfunction "1_1") (pintype "passive"))
      (node (ref "R22") (pin "2") (pinfunction "2_2") (pintype "passive"))
      (node (ref "R23") (pin "1") (pinfunction "1_1") (pintype "passive"))
      (node (ref "R23") (pin "2") (pinfunction "2_2") (pintype "passive"))
      (node (ref "SV2") (pin "1") (pinfunction "1_1") (pintype "passive"))
    )
    (net (code "20") (name "Net-(IC3B-+IN)") (class "Default")
      (node (ref "IC3") (pin "5") (pinfunction "+IN_5") (pintype "input"))
      (node (ref "R14") (pin "1") (pinfunction "1_1") (pintype "passive"))
      (node (ref "R15") (pin "1") (pinfunction "1_1") (pintype "passive"))
    )
    (net (code "21") (name "Net-(IC3B--IN)") (class "Default")
      (node (ref "IC3") (pin "6") (pinfunction "-IN_6") (pintype "input"))
      (node (ref "R16") (pin "2") (pinfunction "2_2") (pintype "passive"))
      (node (ref "R17") (pin "1") (pinfunction "1_1") (pintype "passive"))
    )
    (net (code "22") (name "Net-(IC4A-+IN)") (class "Default")
      (node (ref "IC4") (pin "3") (pinfunction "+IN_3") (pintype "input"))
      (node (ref "IC4") (pin "7") (pinfunction "OUT_7") (pintype "output"))
      (node (ref "R43") (pin "1") (pinfunction "1_1") (pintype "passive"))
    )
    (net (code "23") (name "Net-(IC4A--IN)") (class "Default")
      (node (ref "IC4") (pin "1") (pinfunction "OUT_1") (pintype "output"))
      (node (ref "IC4") (pin "2") (pinfunction "-IN_2") (pintype "input"))
      (node (ref "R49") (pin "1") (pinfunction "1_1") (pintype "passive"))
      (node (ref "R49") (pin "2") (pinfunction "2_2") (pintype "passive"))
      (node (ref "R50") (pin "1") (pinfunction "1_1") (pintype "passive"))
      (node (ref "R50") (pin "2") (pinfunction "2_2") (pintype "passive"))
      (node (ref "SV2") (pin "3") (pinfunction "3_3") (pintype "passive"))
    )
    (net (code "24") (name "Net-(IC4B-+IN)") (class "Default")
      (node (ref "IC4") (pin "5") (pinfunction "+IN_5") (pintype "input"))
      (node (ref "R41") (pin "1") (pinfunction "1_1") (pintype "passive"))
      (node (ref "R42") (pin "1") (pinfunction "1_1") (pintype "passive"))
    )
    (net (code "25") (name "Net-(IC4B--IN)") (class "Default")
      (node (ref "IC4") (pin "6") (pinfunction "-IN_6") (pintype "input"))
      (node (ref "R43") (pin "2") (pinfunction "2_2") (pintype "passive"))
      (node (ref "R44") (pin "1") (pinfunction "1_1") (pintype "passive"))
    )
    (net (code "26") (name "Net-(IC5A-+IN)") (class "Default")
      (node (ref "C38") (pin "1") (pinfunction "1_1") (pintype "passive"))
      (node (ref "IC5") (pin "3") (pinfunction "+IN_3") (pintype "input"))
      (node (ref "R62") (pin "1") (pinfunction "1_1") (pintype "passive"))
    )
    (net (code "27") (name "Net-(IC5A--IN)") (class "Default")
      (node (ref "C37") (pin "1") (pinfunction "1_1") (pintype "passive"))
      (node (ref "IC5") (pin "1") (pinfunction "OUT_1") (pintype "output"))
      (node (ref "IC5") (pin "2") (pinfunction "-IN_2") (pintype "input"))
      (node (ref "R63") (pin "2") (pinfunction "2_2") (pintype "passive"))
    )
    (net (code "28") (name "Net-(IC5B--IN)") (class "Default")
      (node (ref "C39") (pin "2") (pinfunction "2_2") (pintype "passive"))
      (node (ref "IC5") (pin "6") (pinfunction "-IN_6") (pintype "input"))
      (node (ref "R64") (pin "1") (pinfunction "1_1") (pintype "passive"))
    )
    (net (code "29") (name "Net-(IC5B-OUT)") (class "Default")
      (node (ref "C39") (pin "1") (pinfunction "1_1") (pintype "passive"))
      (node (ref "IC5") (pin "7") (pinfunction "OUT_7") (pintype "output"))
      (node (ref "R65") (pin "1") (pinfunction "1_1") (pintype "passive"))
      (node (ref "R69") (pin "2") (pinfunction "2_2") (pintype "passive"))
      (node (ref "R78") (pin "1") (pinfunction "1_1") (pintype "passive"))
      (node (ref "R78") (pin "2") (pinfunction "2_2") (pintype "passive"))
    )
    (net (code "30") (name "Net-(IC6A-+IN)") (class "Default")
      (node (ref "IC6") (pin "3") (pinfunction "+IN_3") (pintype "input"))
      (node (ref "IC6") (pin "7") (pinfunction "OUT_7") (pintype "output"))
      (node (ref "R70") (pin "1") (pinfunction "1_1") (pintype "passive"))
    )
    (net (code "31") (name "Net-(IC6A--IN)") (class "Default")
      (node (ref "IC6") (pin "1") (pinfunction "OUT_1") (pintype "output"))
      (node (ref "IC6") (pin "2") (pinfunction "-IN_2") (pintype "input"))
      (node (ref "R76") (pin "1") (pinfunction "1_1") (pintype "passive"))
      (node (ref "R76") (pin "2") (pinfunction "2_2") (pintype "passive"))
      (node (ref "R77") (pin "1") (pinfunction "1_1") (pintype "passive"))
      (node (ref "R77") (pin "2") (pinfunction "2_2") (pintype "passive"))
      (node (ref "SV2") (pin "5") (pinfunction "5_5") (pintype "passive"))
    )
    (net (code "32") (name "Net-(IC6B-+IN)") (class "Default")
      (node (ref "IC6") (pin "5") (pinfunction "+IN_5") (pintype "input"))
      (node (ref "R68") (pin "1") (pinfunction "1_1") (pintype "passive"))
      (node (ref "R69") (pin "1") (pinfunction "1_1") (pintype "passive"))
    )
    (net (code "33") (name "Net-(IC6B--IN)") (class "Default")
      (node (ref "IC6") (pin "6") (pinfunction "-IN_6") (pintype "input"))
      (node (ref "R70") (pin "2") (pinfunction "2_2") (pintype "passive"))
      (node (ref "R71") (pin "1") (pinfunction "1_1") (pintype "passive"))
    )
    (net (code "34") (name "Net-(INA1-+IN)") (class "Default")
      (node (ref "C19") (pin "2") (pinfunction "2_2") (pintype "passive"))
      (node (ref "C20") (pin "1") (pinfunction "1_1") (pintype "passive"))
      (node (ref "INA1") (pin "4") (pinfunction "+IN_4") (pintype "bidirectional"))
      (node (ref "R30") (pin "1") (pinfunction "1_1") (pintype "passive"))
    )
    (net (code "35") (name "Net-(INA1--IN)") (class "Default")
      (node (ref "C18") (pin "2") (pinfunction "2_2") (pintype "passive"))
      (node (ref "C19") (pin "1") (pinfunction "1_1") (pintype "passive"))
      (node (ref "INA1") (pin "1") (pinfunction "-IN_1") (pintype "input"))
      (node (ref "R29") (pin "1") (pinfunction "1_1") (pintype "passive"))
    )
    (net (code "36") (name "Net-(INA1-REF)") (class "Default")
      (node (ref "C17") (pin "2") (pinfunction "2_2") (pintype "passive"))
      (node (ref "INA1") (pin "6") (pinfunction "REF_6") (pintype "input"))
      (node (ref "R53") (pin "1") (pinfunction "1_1") (pintype "passive"))
      (node (ref "R53") (pin "2") (pinfunction "2_2") (pintype "passive"))
      (node (ref "U$2") (pin "7") (pinfunction "OUT_7") (pintype "output"))
    )
    (net (code "37") (name "Net-(INA1-R_G1)") (class "Default")
      (node (ref "INA1") (pin "2") (pinfunction "R_G1_2") (pintype "bidirectional"))
      (node (ref "R31") (pin "1") (pinfunction "1_1") (pintype "passive"))
    )
    (net (code "38") (name "Net-(INA1-R_G2)") (class "Default")
      (node (ref "INA1") (pin "3") (pinfunction "R_G2_3") (pintype "bidirectional"))
      (node (ref "R31") (pin "2") (pinfunction "2_2") (pintype "passive"))
    )
    (net (code "39") (name "Net-(INA1-V_OUT)") (class "Default")
      (node (ref "INA1") (pin "7") (pinfunction "V_OUT_7") (pintype "output"))
      (node (ref "R28") (pin "2") (pinfunction "2_2") (pintype "passive"))
      (node (ref "R32") (pin "2") (pinfunction "2_2") (pintype "passive"))
    )
    (net (code "40") (name "Net-(INA2-+IN)") (class "Default")
      (node (ref "C35") (pin "2") (pinfunction "2_2") (pintype "passive"))
      (node (ref "C36") (pin "1") (pinfunction "1_1") (pintype "passive"))
      (node (ref "INA2") (pin "4") (pinfunction "+IN_4") (pintype "bidirectional"))
      (node (ref "R57") (pin "1") (pinfunction "1_1") (pintype "passive"))
    )
    (net (code "41") (name "Net-(INA2--IN)") (class "Default")
      (node (ref "C34") (pin "2") (pinfunction "2_2") (pintype "passive"))
      (node (ref "C35") (pin "1") (pinfunction "1_1") (pintype "passive"))
      (node (ref "INA2") (pin "1") (pinfunction "-IN_1") (pintype "input"))
      (node (ref "R56") (pin "1") (pinfunction "1_1") (pintype "passive"))
    )
    (net (code "42") (name "Net-(INA2-REF)") (class "Default")
      (node (ref "C33") (pin "2") (pinfunction "2_2") (pintype "passive"))
      (node (ref "INA2") (pin "6") (pinfunction "REF_6") (pintype "input"))
      (node (ref "R80") (pin "1") (pinfunction "1_1") (pintype "passive"))
      (node (ref "R80") (pin "2") (pinfunction "2_2") (pintype "passive"))
      (node (ref "U$3") (pin "7") (pinfunction "OUT_7") (pintype "output"))
    )
    (net (code "43") (name "Net-(INA2-R_G1)") (class "Default")
      (node (ref "INA2") (pin "2") (pinfunction "R_G1_2") (pintype "bidirectional"))
      (node (ref "R58") (pin "1") (pinfunction "1_1") (pintype "passive"))
    )
    (net (code "44") (name "Net-(INA2-R_G2)") (class "Default")
      (node (ref "INA2") (pin "3") (pinfunction "R_G2_3") (pintype "bidirectional"))
      (node (ref "R58") (pin "2") (pinfunction "2_2") (pintype "passive"))
    )
    (net (code "45") (name "Net-(INA2-V_OUT)") (class "Default")
      (node (ref "INA2") (pin "7") (pinfunction "V_OUT_7") (pintype "output"))
      (node (ref "R55") (pin "2") (pinfunction "2_2") (pintype "passive"))
      (node (ref "R59") (pin "2") (pinfunction "2_2") (pintype "passive"))
    )
    (net (code "46") (name "Net-(INA826-+IN)") (class "Default")
      (node (ref "C2") (pin "1") (pinfunction "1_1") (pintype "passive"))
      (node (ref "C3") (pin "2") (pinfunction "2_2") (pintype "passive"))
      (node (ref "INA826") (pin "4") (pinfunction "+IN_4") (pintype "bidirectional"))
      (node (ref "R2") (pin "1") (pinfunction "1_1") (pintype "passive"))
    )
    (net (code "47") (name "Net-(INA826--IN)") (class "Default")
      (node (ref "C1") (pin "2") (pinfunction "2_2") (pintype "passive"))
      (node (ref "C3") (pin "1") (pinfunction "1_1") (pintype "passive"))
      (node (ref "INA826") (pin "1") (pinfunction "-IN_1") (pintype "input"))
      (node (ref "R1") (pin "1") (pinfunction "1_1") (pintype "passive"))
    )
    (net (code "48") (name "Net-(INA826-REF)") (class "Default")
      (node (ref "C4") (pin "2") (pinfunction "2_2") (pintype "passive"))
      (node (ref "INA826") (pin "6") (pinfunction "REF_6") (pintype "input"))
      (node (ref "R26") (pin "1") (pinfunction "1_1") (pintype "passive"))
      (node (ref "R26") (pin "2") (pinfunction "2_2") (pintype "passive"))
      (node (ref "U$1") (pin "7") (pinfunction "OUT_7") (pintype "output"))
    )
    (net (code "49") (name "Net-(INA826-R_G1)") (class "Default")
      (node (ref "INA826") (pin "2") (pinfunction "R_G1_2") (pintype "bidirectional"))
      (node (ref "R3") (pin "1") (pinfunction "1_1") (pintype "passive"))
    )
    (net (code "50") (name "Net-(INA826-R_G2)") (class "Default")
      (node (ref "INA826") (pin "3") (pinfunction "R_G2_3") (pintype "bidirectional"))
      (node (ref "R3") (pin "2") (pinfunction "2_2") (pintype "passive"))
    )
    (net (code "51") (name "Net-(INA826-V_OUT)") (class "Default")
      (node (ref "INA826") (pin "7") (pinfunction "V_OUT_7") (pintype "output"))
      (node (ref "R4") (pin "2") (pinfunction "2_2") (pintype "passive"))
      (node (ref "R5") (pin "2") (pinfunction "2_2") (pintype "passive"))
    )
    (net (code "52") (name "Net-(R1-Pad2)") (class "Default")
      (node (ref "R1") (pin "2") (pinfunction "2_2") (pintype "passive"))
      (node (ref "SV1") (pin "13") (pinfunction "13_13") (pintype "passive"))
    )
    (net (code "53") (name "Net-(R2-Pad2)") (class "Default")
      (node (ref "R2") (pin "2") (pinfunction "2_2") (pintype "passive"))
      (node (ref "SV1") (pin "11") (pinfunction "11_11") (pintype "passive"))
    )
    (net (code "54") (name "Net-(R12-Pad2)") (class "Default")
      (node (ref "R12") (pin "2") (pinfunction "2_2") (pintype "passive"))
      (node (ref "R13") (pin "1") (pinfunction "1_1") (pintype "passive"))
      (node (ref "R14") (pin "2") (pinfunction "2_2") (pintype "passive"))
    )
    (net (code "55") (name "Net-(R29-Pad2)") (class "Default")
      (node (ref "R29") (pin "2") (pinfunction "2_2") (pintype "passive"))
      (node (ref "SV1") (pin "8") (pinfunction "8_8") (pintype "passive"))
    )
    (net (code "56") (name "Net-(R30-Pad2)") (class "Default")
      (node (ref "R30") (pin "2") (pinfunction "2_2") (pintype "passive"))
      (node (ref "SV1") (pin "7") (pinfunction "7_7") (pintype "passive"))
    )
    (net (code "57") (name "Net-(R39-Pad2)") (class "Default")
      (node (ref "R39") (pin "2") (pinfunction "2_2") (pintype "passive"))
      (node (ref "R40") (pin "1") (pinfunction "1_1") (pintype "passive"))
      (node (ref "R41") (pin "2") (pinfunction "2_2") (pintype "passive"))
    )
    (net (code "58") (name "Net-(R56-Pad2)") (class "Default")
      (node (ref "R56") (pin "2") (pinfunction "2_2") (pintype "passive"))
      (node (ref "SV1") (pin "3") (pinfunction "3_3") (pintype "passive"))
    )
    (net (code "59") (name "Net-(R57-Pad2)") (class "Default")
      (node (ref "R57") (pin "2") (pinfunction "2_2") (pintype "passive"))
      (node (ref "SV1") (pin "1") (pinfunction "1_1") (pintype "passive"))
    )
    (net (code "60") (name "Net-(R66-Pad2)") (class "Default")
      (node (ref "R66") (pin "2") (pinfunction "2_2") (pintype "passive"))
      (node (ref "R67") (pin "1") (pinfunction "1_1") (pintype "passive"))
      (node (ref "R68") (pin "2") (pinfunction "2_2") (pintype "passive"))
    )
    (net (code "61") (name "Net-(U$1A--IN)") (class "Default")
      (node (ref "R18") (pin "1") (pinfunction "1_1") (pintype "passive"))
      (node (ref "R18") (pin "2") (pinfunction "2_2") (pintype "passive"))
      (node (ref "R20") (pin "1") (pinfunction "1_1") (pintype "passive"))
      (node (ref "R20") (pin "2") (pinfunction "2_2") (pintype "passive"))
      (node (ref "R5") (pin "1") (pinfunction "1_1") (pintype "passive"))
      (node (ref "R6") (pin "2") (pinfunction "2_2") (pintype "passive"))
      (node (ref "U$1") (pin "2") (pinfunction "-IN_2") (pintype "input"))
    )
    (net (code "62") (name "Net-(U$1A-OUT)") (class "Default")
      (node (ref "R19") (pin "1") (pinfunction "1_1") (pintype "passive"))
      (node (ref "R19") (pin "2") (pinfunction "2_2") (pintype "passive"))
      (node (ref "R6") (pin "1") (pinfunction "1_1") (pintype "passive"))
      (node (ref "R7") (pin "2") (pinfunction "2_2") (pintype "passive"))
      (node (ref "U$1") (pin "1") (pinfunction "OUT_1") (pintype "output"))
    )
    (net (code "63") (name "Net-(U$1B--IN)") (class "Default")
      (node (ref "C4") (pin "1") (pinfunction "1_1") (pintype "passive"))
      (node (ref "R4") (pin "1") (pinfunction "1_1") (pintype "passive"))
      (node (ref "U$1") (pin "6") (pinfunction "-IN_6") (pintype "input"))
    )
    (net (code "64") (name "Net-(U$2A--IN)") (class "Default")
      (node (ref "R32") (pin "1") (pinfunction "1_1") (pintype "passive"))
      (node (ref "R33") (pin "2") (pinfunction "2_2") (pintype "passive"))
      (node (ref "R45") (pin "1") (pinfunction "1_1") (pintype "passive"))
      (node (ref "R45") (pin "2") (pinfunction "2_2") (pintype "passive"))
      (node (ref "R47") (pin "1") (pinfunction "1_1") (pintype "passive"))
      (node (ref "R47") (pin "2") (pinfunction "2_2") (pintype "passive"))
      (node (ref "U$2") (pin "2") (pinfunction "-IN_2") (pintype "input"))
    )
    (net (code "65") (name "Net-(U$2A-OUT)") (class "Default")
      (node (ref "R33") (pin "1") (pinfunction "1_1") (pintype "passive"))
      (node (ref "R34") (pin "2") (pinfunction "2_2") (pintype "passive"))
      (node (ref "R46") (pin "1") (pinfunction "1_1") (pintype "passive"))
      (node (ref "R46") (pin "2") (pinfunction "2_2") (pintype "passive"))
      (node (ref "U$2") (pin "1") (pinfunction "OUT_1") (pintype "output"))
    )
    (net (code "66") (name "Net-(U$2B--IN)") (class "Default")
      (node (ref "C17") (pin "1") (pinfunction "1_1") (pintype "passive"))
      (node (ref "R28") (pin "1") (pinfunction "1_1") (pintype "passive"))
      (node (ref "U$2") (pin "6") (pinfunction "-IN_6") (pintype "input"))
    )
    (net (code "67") (name "Net-(U$3A--IN)") (class "Default")
      (node (ref "R59") (pin "1") (pinfunction "1_1") (pintype "passive"))
      (node (ref "R60") (pin "2") (pinfunction "2_2") (pintype "passive"))
      (node (ref "R72") (pin "1") (pinfunction "1_1") (pintype "passive"))
      (node (ref "R72") (pin "2") (pinfunction "2_2") (pintype "passive"))
      (node (ref "R74") (pin "1") (pinfunction "1_1") (pintype "passive"))
      (node (ref "R74") (pin "2") (pinfunction "2_2") (pintype "passive"))
      (node (ref "U$3") (pin "2") (pinfunction "-IN_2") (pintype "input"))
    )
    (net (code "68") (name "Net-(U$3A-OUT)") (class "Default")
      (node (ref "R60") (pin "1") (pinfunction "1_1") (pintype "passive"))
      (node (ref "R61") (pin "2") (pinfunction "2_2") (pintype "passive"))
      (node (ref "R73") (pin "1") (pinfunction "1_1") (pintype "passive"))
      (node (ref "R73") (pin "2") (pinfunction "2_2") (pintype "passive"))
      (node (ref "U$3") (pin "1") (pinfunction "OUT_1") (pintype "output"))
    )
    (net (code "69") (name "Net-(U$3B--IN)") (class "Default")
      (node (ref "C33") (pin "1") (pinfunction "1_1") (pintype "passive"))
      (node (ref "R55") (pin "1") (pinfunction "1_1") (pintype "passive"))
      (node (ref "U$3") (pin "6") (pinfunction "-IN_6") (pintype "input"))
    )
  )
)
